# sodaled.net
KiCad netlist of a schematic drawn in EAGLE
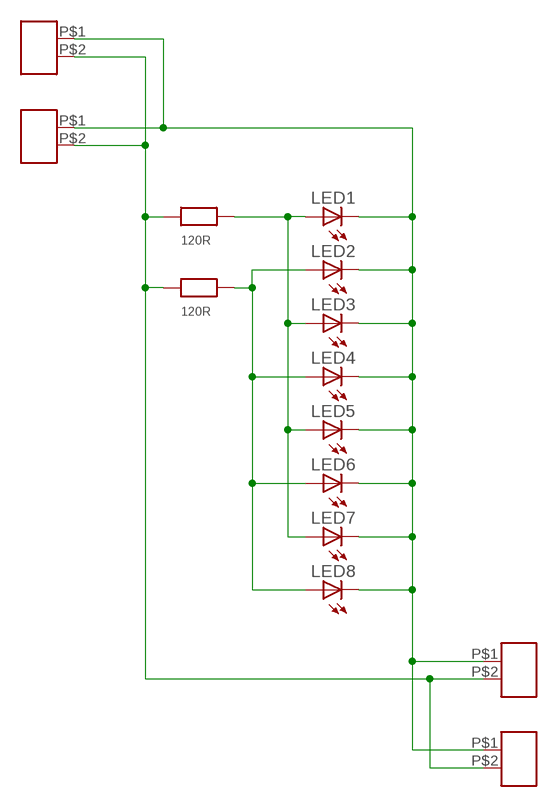
[diagram p0: schematic, sheet 1]

(export (version "E")
  (design (tool "Eeschema 10.0.6"))
  (components
    (comp (ref "LED1")
      (value "LEDRECT_SIDE")
      (footprint "eagle-import:LED_RECT_SIDEMOUNT")
      (libsource (lib "eagle-import") (part "LEDRECT_SIDE"))
    )
    (comp (ref "LED2")
      (value "LEDRECT_SIDE")
      (footprint "eagle-import:LED_RECT_SIDEMOUNT")
      (libsource (lib "eagle-import") (part "LEDRECT_SIDE"))
    )
    (comp (ref "LED3")
      (value "LEDRECT_SIDE")
      (footprint "eagle-import:LED_RECT_SIDEMOUNT")
      (libsource (lib "eagle-import") (part "LEDRECT_SIDE"))
    )
    (comp (ref "LED4")
      (value "LEDRECT_SIDE")
      (footprint "eagle-import:LED_RECT_SIDEMOUNT")
      (libsource (lib "eagle-import") (part "LEDRECT_SIDE"))
    )
    (comp (ref "LED5")
      (value "LEDRECT_SIDE")
      (footprint "eagle-import:LED_RECT_SIDEMOUNT")
      (libsource (lib "eagle-import") (part "LEDRECT_SIDE"))
    )
    (comp (ref "LED6")
      (value "LEDRECT_SIDE")
      (footprint "eagle-import:LED_RECT_SIDEMOUNT")
      (libsource (lib "eagle-import") (part "LEDRECT_SIDE"))
    )
    (comp (ref "LED7")
      (value "LEDRECT_SIDE")
      (footprint "eagle-import:LED_RECT_SIDEMOUNT")
      (libsource (lib "eagle-import") (part "LEDRECT_SIDE"))
    )
    (comp (ref "LED8")
      (value "LEDRECT_SIDE")
      (footprint "eagle-import:LED_RECT_SIDEMOUNT")
      (libsource (lib "eagle-import") (part "LEDRECT_SIDE"))
    )
    (comp (ref "U$1")
      (value "M02")
      (footprint "eagle-import:1X02")
      (libsource (lib "eagle-import") (part "M02"))
    )
    (comp (ref "U$2")
      (value "M02")
      (footprint "eagle-import:1X02")
      (libsource (lib "eagle-import") (part "M02"))
    )
    (comp (ref "U$3")
      (value "M02")
      (footprint "eagle-import:1X02")
      (libsource (lib "eagle-import") (part "M02"))
    )
    (comp (ref "U$4")
      (value "M02")
      (footprint "eagle-import:1X02")
      (libsource (lib "eagle-import") (part "M02"))
    )
    (comp (ref "U$7")
      (value "120R")
      (footprint "eagle-import:RESISTOR_CFM1")
      (libsource (lib "eagle-import") (part "RESISTOR"))
    )
    (comp (ref "U$8")
      (value "120R")
      (footprint "eagle-import:RESISTOR_CFM1")
      (libsource (lib "eagle-import") (part "RESISTOR"))
    )
  )
  (nets
    (net (code "1") (name "Net-(LED1-PadA)") (class "Default")
      (node (ref "LED1") (pin "A") (pinfunction "A_A") (pintype "passive"))
      (node (ref "LED3") (pin "A") (pinfunction "A_A") (pintype "passive"))
      (node (ref "LED5") (pin "A") (pinfunction "A_A") (pintype "passive"))
      (node (ref "LED7") (pin "A") (pinfunction "A_A") (pintype "passive"))
      (node (ref "U$7") (pin "P$2") (pinfunction "P$2_P$2") (pintype "bidirectional"))
    )
    (net (code "2") (name "Net-(LED1-PadC)") (class "Default")
      (node (ref "LED1") (pin "C") (pinfunction "C_C") (pintype "passive"))
      (node (ref "LED2") (pin "C") (pinfunction "C_C") (pintype "passive"))
      (node (ref "LED3") (pin "C") (pinfunction "C_C") (pintype "passive"))
      (node (ref "LED4") (pin "C") (pinfunction "C_C") (pintype "passive"))
      (node (ref "LED5") (pin "C") (pinfunction "C_C") (pintype "passive"))
      (node (ref "LED6") (pin "C") (pinfunction "C_C") (pintype "passive"))
      (node (ref "LED7") (pin "C") (pinfunction "C_C") (pintype "passive"))
      (node (ref "LED8") (pin "C") (pinfunction "C_C") (pintype "passive"))
      (node (ref "U$1") (pin "P$1") (pinfunction "P$1_P$1") (pintype "bidirectional"))
      (node (ref "U$2") (pin "P$1") (pinfunction "P$1_P$1") (pintype "bidirectional"))
      (node (ref "U$3") (pin "P$1") (pinfunction "P$1_P$1") (pintype "bidirectional"))
      (node (ref "U$4") (pin "P$1") (pinfunction "P$1_P$1") (pintype "bidirectional"))
    )
    (net (code "3") (name "Net-(LED2-PadA)") (class "Default")
      (node (ref "LED2") (pin "A") (pinfunction "A_A") (pintype "passive"))
      (node (ref "LED4") (pin "A") (pinfunction "A_A") (pintype "passive"))
      (node (ref "LED6") (pin "A") (pinfunction "A_A") (pintype "passive"))
      (node (ref "LED8") (pin "A") (pinfunction "A_A") (pintype "passive"))
      (node (ref "U$8") (pin "P$2") (pinfunction "P$2_P$2") (pintype "bidirectional"))
    )
    (net (code "4") (name "Net-(U$1-PadP$2)") (class "Default")
      (node (ref "U$1") (pin "P$2") (pinfunction "P$2_P$2") (pintype "bidirectional"))
      (node (ref "U$2") (pin "P$2") (pinfunction "P$2_P$2") (pintype "bidirectional"))
      (node (ref "U$3") (pin "P$2") (pinfunction "P$2_P$2") (pintype "bidirectional"))
      (node (ref "U$4") (pin "P$2") (pinfunction "P$2_P$2") (pintype "bidirectional"))
      (node (ref "U$7") (pin "P$1") (pinfunction "P$1_P$1") (pintype "bidirectional"))
      (node (ref "U$8") (pin "P$1") (pinfunction "P$1_P$1") (pintype "bidirectional"))
    )
  )
)
